# Parallel_Data_Interface_Demo.net
KiCad netlist of a schematic drawn in Altium Designer
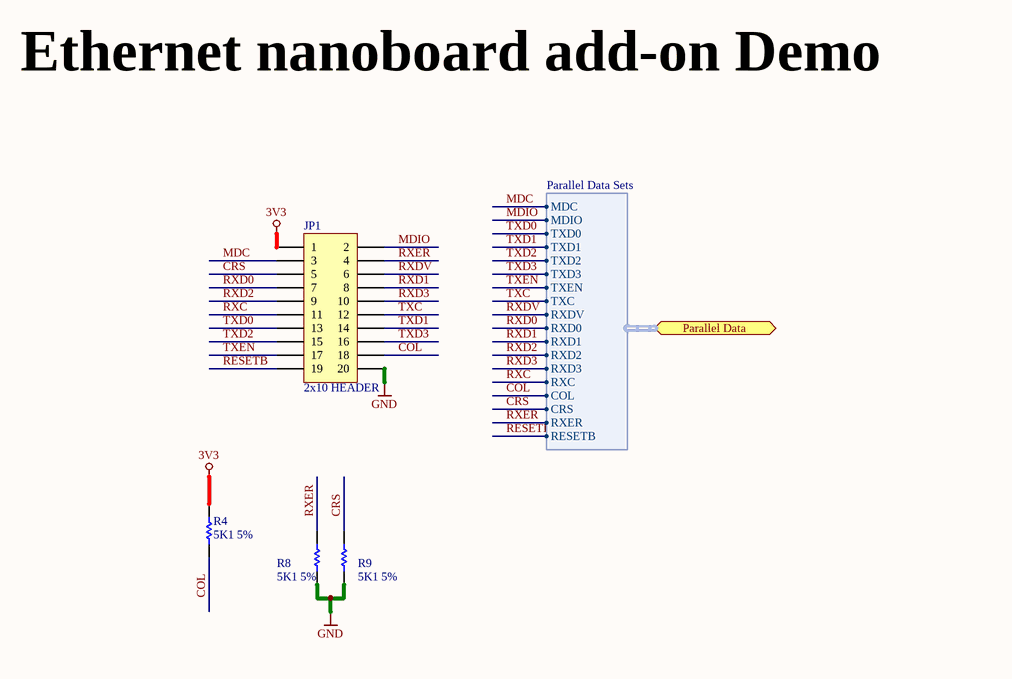
[diagram p0: Parallel Data Interface_Demo.SchDoc]

(export (version "E")
  (design (tool "Eeschema 10.0.6"))
  (components
    (comp (ref "JP1")
      (value "2x10 HEADER")
      (footprint "PHY_Demo:HDR2X10")
      (description "Header, 10-Pin, Dual row")
      (libsource (lib "Altium Design Library") (part "CON-HDR-2x10-STR"))
    )
    (comp (ref "R4")
      (value "5K1 5%")
      (footprint "PHY_Demo:RESC2012")
      (description "Resistor")
      (libsource (lib "Altium Design Library") (part "RES"))
    )
    (comp (ref "R8")
      (value "5K1 5%")
      (footprint "PHY_Demo:RESC2012")
      (description "Resistor")
      (libsource (lib "Altium Design Library") (part "RES"))
    )
    (comp (ref "R9")
      (value "5K1 5%")
      (footprint "PHY_Demo:RESC2012")
      (description "Resistor")
      (libsource (lib "Altium Design Library") (part "RES"))
    )
  )
  (nets
    (net (code "4") (name "/COL") (class "Default")
      (node (ref "JP1") (pin "18") (pinfunction "18_18") (pintype "passive"))
      (node (ref "R4") (pin "1") (pinfunction "1_1") (pintype "passive"))
    )
    (net (code "5") (name "/CRS") (class "Default")
      (node (ref "JP1") (pin "5") (pinfunction "5_5") (pintype "passive"))
      (node (ref "R9") (pin "2") (pinfunction "2_2") (pintype "passive"))
    )
    (net (code "6") (name "/MDC") (class "Default")
      (node (ref "JP1") (pin "3") (pinfunction "3_3") (pintype "passive"))
    )
    (net (code "7") (name "/MDIO") (class "Default")
      (node (ref "JP1") (pin "2") (pinfunction "2_2") (pintype "passive"))
    )
    (net (code "8") (name "/RESETB") (class "Default")
      (node (ref "JP1") (pin "19") (pinfunction "19_19") (pintype "passive"))
    )
    (net (code "9") (name "/RXC") (class "Default")
      (node (ref "JP1") (pin "11") (pinfunction "11_11") (pintype "passive"))
    )
    (net (code "10") (name "/RXD0") (class "Default")
      (node (ref "JP1") (pin "7") (pinfunction "7_7") (pintype "passive"))
    )
    (net (code "11") (name "/RXD1") (class "Default")
      (node (ref "JP1") (pin "8") (pinfunction "8_8") (pintype "passive"))
    )
    (net (code "12") (name "/RXD2") (class "Default")
      (node (ref "JP1") (pin "9") (pinfunction "9_9") (pintype "passive"))
    )
    (net (code "13") (name "/RXD3") (class "Default")
      (node (ref "JP1") (pin "10") (pinfunction "10_10") (pintype "passive"))
    )
    (net (code "14") (name "/RXDV") (class "Default")
      (node (ref "JP1") (pin "6") (pinfunction "6_6") (pintype "passive"))
    )
    (net (code "15") (name "/RXER") (class "Default")
      (node (ref "JP1") (pin "4") (pinfunction "4_4") (pintype "passive"))
      (node (ref "R8") (pin "2") (pinfunction "2_2") (pintype "passive"))
    )
    (net (code "16") (name "/TXC") (class "Default")
      (node (ref "JP1") (pin "12") (pinfunction "12_12") (pintype "passive"))
    )
    (net (code "17") (name "/TXD0") (class "Default")
      (node (ref "JP1") (pin "13") (pinfunction "13_13") (pintype "passive"))
    )
    (net (code "18") (name "/TXD1") (class "Default")
      (node (ref "JP1") (pin "14") (pinfunction "14_14") (pintype "passive"))
    )
    (net (code "19") (name "/TXD2") (class "Default")
      (node (ref "JP1") (pin "15") (pinfunction "15_15") (pintype "passive"))
    )
    (net (code "20") (name "/TXD3") (class "Default")
      (node (ref "JP1") (pin "16") (pinfunction "16_16") (pintype "passive"))
    )
    (net (code "21") (name "/TXEN") (class "Default")
      (node (ref "JP1") (pin "17") (pinfunction "17_17") (pintype "passive"))
    )
    (net (code "23") (name "3V3") (class "Default")
      (node (ref "JP1") (pin "1") (pinfunction "1_1") (pintype "passive"))
      (node (ref "R4") (pin "2") (pinfunction "2_2") (pintype "passive"))
    )
    (net (code "24") (name "GND") (class "Default")
      (node (ref "JP1") (pin "20") (pinfunction "20_20") (pintype "passive"))
      (node (ref "R8") (pin "1") (pinfunction "1_1") (pintype "passive"))
      (node (ref "R9") (pin "1") (pinfunction "1_1") (pintype "passive"))
    )
  )
)
